# shinobi_5v_3V3_dcdc_jack.net
KiCad netlist of a schematic drawn in EAGLE
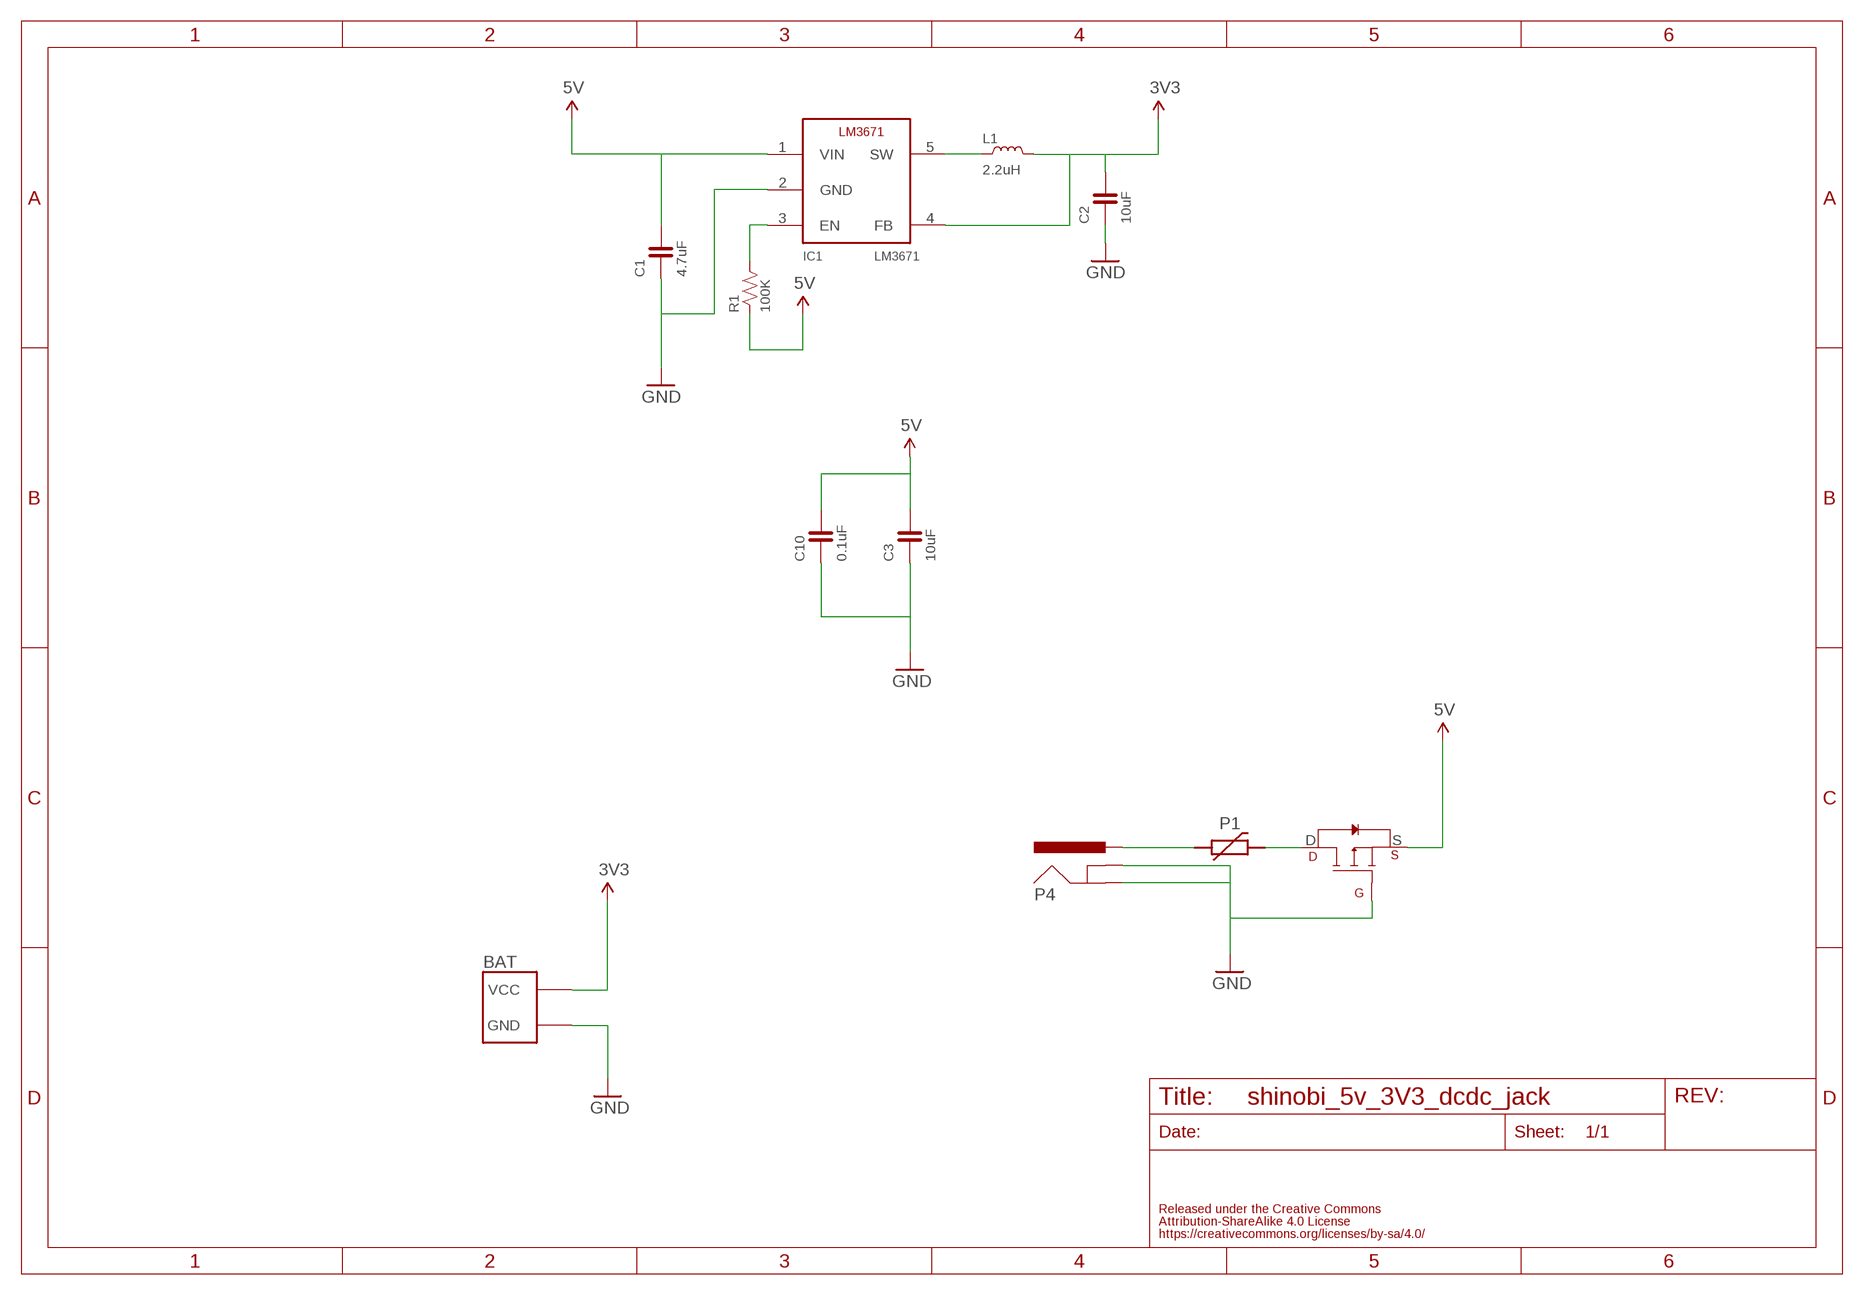
[diagram p0: schematic, sheet 1]

(export (version "E")
  (design (tool "Eeschema 10.0.6"))
  (components
    (comp (ref "BAT")
      (value "FABO_BRICK_2PIN_SIDE")
      (footprint "eagle-import:FABO_BRICK_2PIN_S02B−PASK-2_SILK")
      (libsource (lib "eagle-import") (part "FABO_BRICK_2PIN_SIDE"))
    )
    (comp (ref "C1")
      (value "4.7uF")
      (footprint "eagle-import:0603")
      (libsource (lib "eagle-import") (part "CAPACITOR-0603"))
    )
    (comp (ref "C2")
      (value "10uF")
      (footprint "eagle-import:0603")
      (libsource (lib "eagle-import") (part "CAPACITOR-0603"))
    )
    (comp (ref "C3")
      (value "10uF")
      (footprint "eagle-import:0603")
      (libsource (lib "eagle-import") (part "CAPACITOR-0603"))
    )
    (comp (ref "C10")
      (value "0.1uF")
      (footprint "eagle-import:0603")
      (libsource (lib "eagle-import") (part "CAPACITOR-0603"))
    )
    (comp (ref "IC1")
      (value "LM3671")
      (footprint "eagle-import:LM3671")
      (libsource (lib "eagle-import") (part "LM3671"))
    )
    (comp (ref "L1")
      (value "2.2uH")
      (footprint "eagle-import:2.4X2.4")
      (libsource (lib "eagle-import") (part "INDUCTOR2.4X2.4"))
    )
    (comp (ref "M1")
      (value "AOD417")
      (footprint "eagle-import:AOD417")
      (libsource (lib "eagle-import") (part "AOD417"))
    )
    (comp (ref "P1")
      (value "POLYSWITCH1210")
      (footprint "eagle-import:1210")
      (libsource (lib "eagle-import") (part "POLYSWITCH1210"))
    )
    (comp (ref "P4")
      (value "DC-JACK2DC-G232-B66")
      (footprint "eagle-import:2DC-G213-B66")
      (libsource (lib "eagle-import") (part "DC-JACK2DC-G232-B66"))
    )
    (comp (ref "R1")
      (value "100K")
      (footprint "eagle-import:0603")
      (libsource (lib "eagle-import") (part "RESISTOR-0603"))
    )
  )
  (nets
    (net (code "1") (name "3V3") (class "Default")
      (node (ref "BAT") (pin "VCC") (pinfunction "VCC_VCC") (pintype "bidirectional"))
      (node (ref "C2") (pin "2") (pinfunction "2_2") (pintype "passive"))
      (node (ref "IC1") (pin "4") (pinfunction "FB_4") (pintype "bidirectional"))
      (node (ref "L1") (pin "P$2") (pinfunction "2_P$2") (pintype "bidirectional"))
    )
    (net (code "2") (name "5V") (class "Default")
      (node (ref "C1") (pin "2") (pinfunction "2_2") (pintype "passive"))
      (node (ref "C10") (pin "2") (pinfunction "2_2") (pintype "passive"))
      (node (ref "C3") (pin "2") (pinfunction "2_2") (pintype "passive"))
      (node (ref "IC1") (pin "1") (pinfunction "VIN_1") (pintype "bidirectional"))
      (node (ref "M1") (pin "S") (pinfunction "S_S") (pintype "bidirectional"))
      (node (ref "R1") (pin "1") (pinfunction "1_1") (pintype "bidirectional"))
    )
    (net (code "3") (name "GND") (class "Default")
      (node (ref "BAT") (pin "GND") (pinfunction "GND_GND") (pintype "bidirectional"))
      (node (ref "C1") (pin "1") (pinfunction "1_1") (pintype "passive"))
      (node (ref "C10") (pin "1") (pinfunction "1_1") (pintype "passive"))
      (node (ref "C2") (pin "1") (pinfunction "1_1") (pintype "passive"))
      (node (ref "C3") (pin "1") (pinfunction "1_1") (pintype "passive"))
      (node (ref "IC1") (pin "2") (pinfunction "GND_2") (pintype "bidirectional"))
      (node (ref "M1") (pin "G") (pinfunction "G_G") (pintype "bidirectional"))
      (node (ref "P4") (pin "GND") (pinfunction "GND_GND") (pintype "bidirectional"))
      (node (ref "P4") (pin "GND-BREAKE@2") (pinfunction "GNDBREAK_GND-BREAKE@2") (pintype "bidirectional"))
      (node (ref "P4") (pin "GND-BREAKER@1") (pinfunction "GNDBREAK_GND-BREAKER@1") (pintype "bidirectional"))
      (node (ref "P4") (pin "GND-BREAKER@3") (pinfunction "GNDBREAK_GND-BREAKER@3") (pintype "bidirectional"))
      (node (ref "P4") (pin "GND-BREAKER@4") (pinfunction "GNDBREAK_GND-BREAKER@4") (pintype "bidirectional"))
    )
    (net (code "4") (name "Net-(IC1-EN)") (class "Default")
      (node (ref "IC1") (pin "3") (pinfunction "EN_3") (pintype "bidirectional"))
      (node (ref "R1") (pin "2") (pinfunction "2_2") (pintype "bidirectional"))
    )
    (net (code "5") (name "Net-(IC1-SW)") (class "Default")
      (node (ref "IC1") (pin "5") (pinfunction "SW_5") (pintype "bidirectional"))
      (node (ref "L1") (pin "P$1") (pinfunction "1_P$1") (pintype "bidirectional"))
    )
    (net (code "6") (name "Net-(P1-1)") (class "Default")
      (node (ref "P1") (pin "P$1") (pinfunction "1_P$1") (pintype "bidirectional"))
      (node (ref "P4") (pin "VCC") (pinfunction "PWR_VCC") (pintype "bidirectional"))
    )
    (net (code "7") (name "Net-(P1-2)") (class "Default")
      (node (ref "M1") (pin "D") (pinfunction "D_D") (pintype "bidirectional"))
      (node (ref "P1") (pin "P$2") (pinfunction "2_P$2") (pintype "bidirectional"))
    )
  )
)
